# DriverV1_0.net
KiCad netlist of a schematic drawn in Altium Designer
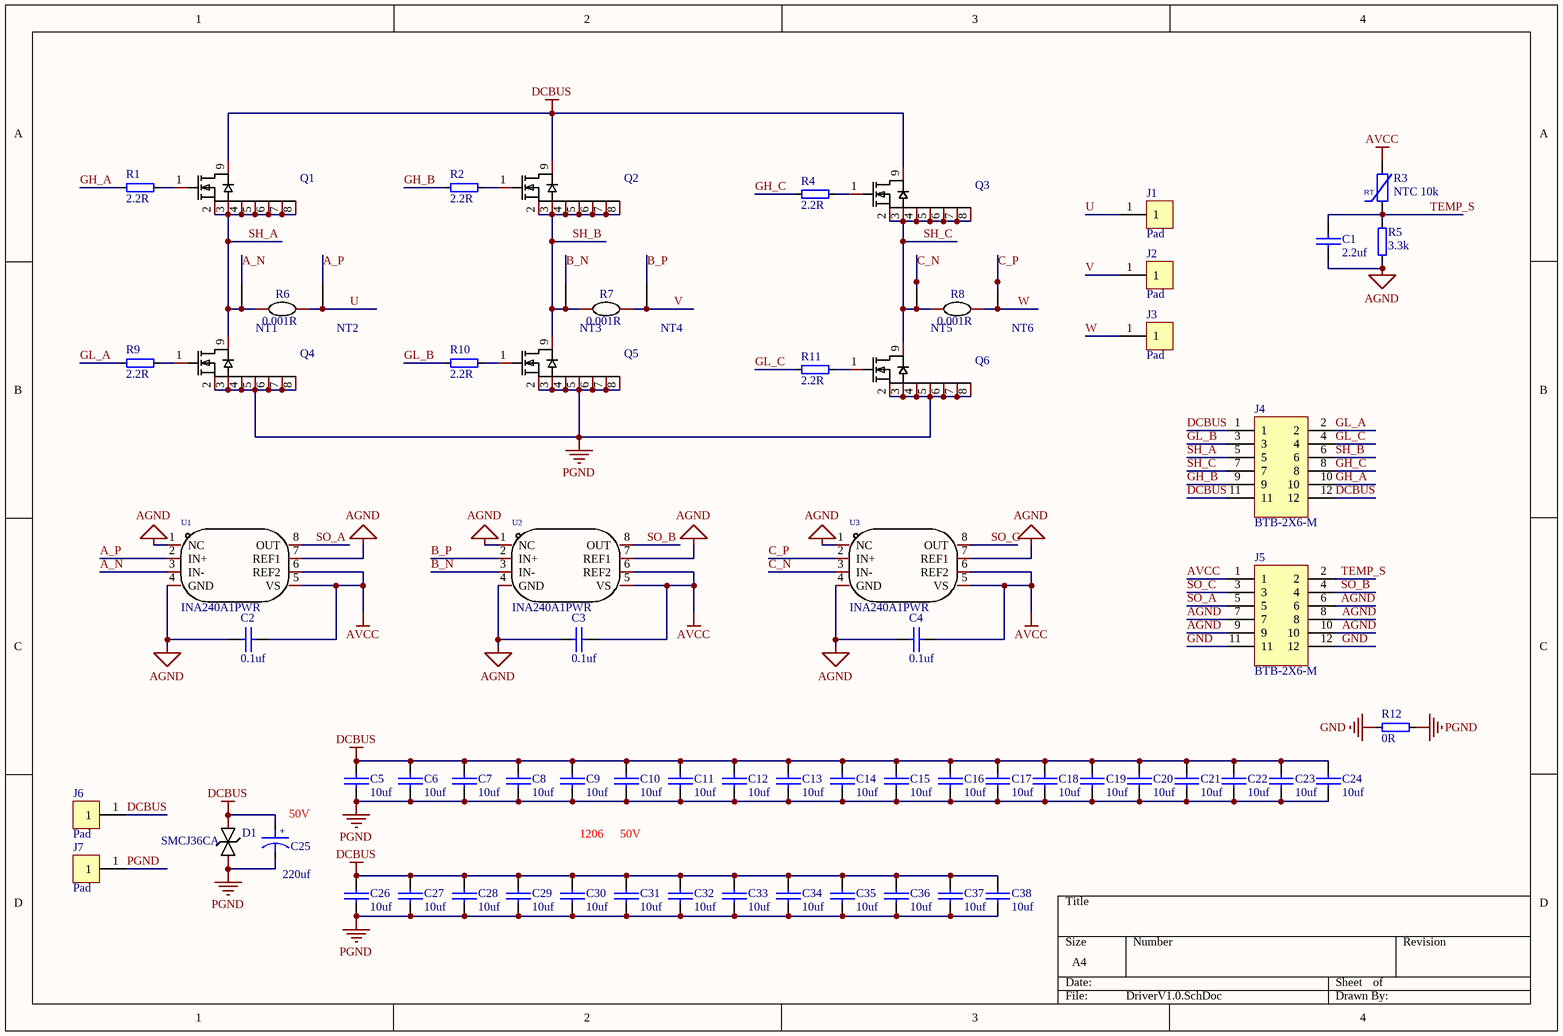
[diagram p0: DriverV1.0.SchDoc]

(export (version "E")
  (design (tool "Eeschema 10.0.6"))
  (components
    (comp (ref "C1")
      (value "2.2uf")
      (footprint "0603C")
      (description "贴片电容")
      (libsource (lib "Driver") (part "CAP"))
    )
    (comp (ref "C2")
      (value "0.1uf")
      (footprint "0603C")
      (description "贴片电容")
      (libsource (lib "Driver") (part "CAP"))
    )
    (comp (ref "C3")
      (value "0.1uf")
      (footprint "0603C")
      (description "贴片电容")
      (libsource (lib "Driver") (part "CAP"))
    )
    (comp (ref "C4")
      (value "0.1uf")
      (footprint "0603C")
      (description "贴片电容")
      (libsource (lib "Driver") (part "CAP"))
    )
    (comp (ref "C5")
      (value "10uf")
      (footprint "1206C")
      (description "贴片电容")
      (libsource (lib "Driver") (part "CAP"))
    )
    (comp (ref "C6")
      (value "10uf")
      (footprint "1206C")
      (description "贴片电容")
      (libsource (lib "Driver") (part "CAP"))
    )
    (comp (ref "C7")
      (value "10uf")
      (footprint "1206C")
      (description "贴片电容")
      (libsource (lib "Driver") (part "CAP"))
    )
    (comp (ref "C8")
      (value "10uf")
      (footprint "1206C")
      (description "贴片电容")
      (libsource (lib "Driver") (part "CAP"))
    )
    (comp (ref "C9")
      (value "10uf")
      (footprint "1206C")
      (description "贴片电容")
      (libsource (lib "Driver") (part "CAP"))
    )
    (comp (ref "C10")
      (value "10uf")
      (footprint "1206C")
      (description "贴片电容")
      (libsource (lib "Driver") (part "CAP"))
    )
    (comp (ref "C11")
      (value "10uf")
      (footprint "1206C")
      (description "贴片电容")
      (libsource (lib "Driver") (part "CAP"))
    )
    (comp (ref "C12")
      (value "10uf")
      (footprint "1206C")
      (description "贴片电容")
      (libsource (lib "Driver") (part "CAP"))
    )
    (comp (ref "C13")
      (value "10uf")
      (footprint "1206C")
      (description "贴片电容")
      (libsource (lib "Driver") (part "CAP"))
    )
    (comp (ref "C14")
      (value "10uf")
      (footprint "1206C")
      (description "贴片电容")
      (libsource (lib "Driver") (part "CAP"))
    )
    (comp (ref "C15")
      (value "10uf")
      (footprint "1206C")
      (description "贴片电容")
      (libsource (lib "Driver") (part "CAP"))
    )
    (comp (ref "C16")
      (value "10uf")
      (footprint "1206C")
      (description "贴片电容")
      (libsource (lib "Driver") (part "CAP"))
    )
    (comp (ref "C17")
      (value "10uf")
      (footprint "1206C")
      (description "贴片电容")
      (libsource (lib "Driver") (part "CAP"))
    )
    (comp (ref "C18")
      (value "10uf")
      (footprint "1206C")
      (description "贴片电容")
      (libsource (lib "Driver") (part "CAP"))
    )
    (comp (ref "C19")
      (value "10uf")
      (footprint "1206C")
      (description "贴片电容")
      (libsource (lib "Driver") (part "CAP"))
    )
    (comp (ref "C20")
      (value "10uf")
      (footprint "1206C")
      (description "贴片电容")
      (libsource (lib "Driver") (part "CAP"))
    )
    (comp (ref "C21")
      (value "10uf")
      (footprint "1206C")
      (description "贴片电容")
      (libsource (lib "Driver") (part "CAP"))
    )
    (comp (ref "C22")
      (value "10uf")
      (footprint "1206C")
      (description "贴片电容")
      (libsource (lib "Driver") (part "CAP"))
    )
    (comp (ref "C23")
      (value "10uf")
      (footprint "1206C")
      (description "贴片电容")
      (libsource (lib "Driver") (part "CAP"))
    )
    (comp (ref "C24")
      (value "10uf")
      (footprint "1206C")
      (description "贴片电容")
      (libsource (lib "Driver") (part "CAP"))
    )
    (comp (ref "C25")
      (value "220uf")
      (footprint "ELECTRO10-5-N")
      (description "极性电容")
      (libsource (lib "Driver") (part "CAP+"))
    )
    (comp (ref "C26")
      (value "10uf")
      (footprint "1206C")
      (description "贴片电容")
      (libsource (lib "Driver") (part "CAP"))
    )
    (comp (ref "C27")
      (value "10uf")
      (footprint "1206C")
      (description "贴片电容")
      (libsource (lib "Driver") (part "CAP"))
    )
    (comp (ref "C28")
      (value "10uf")
      (footprint "1206C")
      (description "贴片电容")
      (libsource (lib "Driver") (part "CAP"))
    )
    (comp (ref "C29")
      (value "10uf")
      (footprint "1206C")
      (description "贴片电容")
      (libsource (lib "Driver") (part "CAP"))
    )
    (comp (ref "C30")
      (value "10uf")
      (footprint "1206C")
      (description "贴片电容")
      (libsource (lib "Driver") (part "CAP"))
    )
    (comp (ref "C31")
      (value "10uf")
      (footprint "1206C")
      (description "贴片电容")
      (libsource (lib "Driver") (part "CAP"))
    )
    (comp (ref "C32")
      (value "10uf")
      (footprint "1206C")
      (description "贴片电容")
      (libsource (lib "Driver") (part "CAP"))
    )
    (comp (ref "C33")
      (value "10uf")
      (footprint "1206C")
      (description "贴片电容")
      (libsource (lib "Driver") (part "CAP"))
    )
    (comp (ref "C34")
      (value "10uf")
      (footprint "1206C")
      (description "贴片电容")
      (libsource (lib "Driver") (part "CAP"))
    )
    (comp (ref "C35")
      (value "10uf")
      (footprint "1206C")
      (description "贴片电容")
      (libsource (lib "Driver") (part "CAP"))
    )
    (comp (ref "C36")
      (value "10uf")
      (footprint "1206C")
      (description "贴片电容")
      (libsource (lib "Driver") (part "CAP"))
    )
    (comp (ref "C37")
      (value "10uf")
      (footprint "1206C")
      (description "贴片电容")
      (libsource (lib "Driver") (part "CAP"))
    )
    (comp (ref "C38")
      (value "10uf")
      (footprint "1206C")
      (description "贴片电容")
      (libsource (lib "Driver") (part "CAP"))
    )
    (comp (ref "D1")
      (value "SMCJ36CA")
      (footprint "SMC")
      (description "极性:双向;")
      (fields (field (name "MANUFACTURER") "TWGMC(台湾迪嘉)") (field (name "MANUFACTURER PART") "SMBJ28CA"))
      (libsource (lib "Driver") (part "SMCJ36CA"))
    )
    (comp (ref "J1")
      (value "Pad")
      (footprint "PAD")
      (description "焊盘")
      (libsource (lib "Driver") (part "Pad"))
    )
    (comp (ref "J2")
      (value "Pad")
      (footprint "PAD")
      (description "焊盘")
      (libsource (lib "Driver") (part "Pad"))
    )
    (comp (ref "J3")
      (value "Pad")
      (footprint "PAD")
      (description "焊盘")
      (libsource (lib "Driver") (part "Pad"))
    )
    (comp (ref "J4")
      (value "BTB-2X6-M")
      (footprint "BTB-M-0.8mm-2x6P")
      (description "0.8间距2x6P公座")
      (libsource (lib "Driver") (part "BTB-2X6-M"))
    )
    (comp (ref "J5")
      (value "BTB-2X6-M")
      (footprint "BTB-M-0.8mm-2x6P")
      (description "0.8间距2x6P公座")
      (libsource (lib "Driver") (part "BTB-2X6-M"))
    )
    (comp (ref "J6") (value "Pad") (footprint "PAD") (description "焊盘") (libsource (lib "") (part "Pad_1")))
    (comp (ref "J7") (value "Pad") (footprint "PAD") (description "焊盘") (libsource (lib "") (part "Pad_1")))
    (comp (ref "NT1")
      (value "0.25mm")
      (footprint "NetTie_0.25mm")
      (libsource (lib "Driver") (part "NetTie_0.25mm"))
    )
    (comp (ref "NT2")
      (value "0.25mm")
      (footprint "NetTie_0.25mm")
      (libsource (lib "Driver") (part "NetTie_0.25mm"))
    )
    (comp (ref "NT3")
      (value "0.25mm")
      (footprint "NetTie_0.25mm")
      (libsource (lib "Driver") (part "NetTie_0.25mm"))
    )
    (comp (ref "NT4")
      (value "0.25mm")
      (footprint "NetTie_0.25mm")
      (libsource (lib "Driver") (part "NetTie_0.25mm"))
    )
    (comp (ref "NT5")
      (value "0.25mm")
      (footprint "NetTie_0.25mm")
      (libsource (lib "Driver") (part "NetTie_0.25mm"))
    )
    (comp (ref "NT6")
      (value "0.25mm")
      (footprint "NetTie_0.25mm")
      (libsource (lib "Driver") (part "NetTie_0.25mm"))
    )
    (comp (ref "Q1")
      (value "HYG006N04LS1TA")
      (footprint "TOLL")
      (description "N沟道增强型MOS 40V-600A")
      (fields (field (name "MANUFACTURER") "HUAYI(华羿微)"))
      (libsource (lib "Driver") (part "HYG006N04LS1TA"))
    )
    (comp (ref "Q2")
      (value "HYG006N04LS1TA")
      (footprint "TOLL")
      (description "N沟道增强型MOS 40V-600A")
      (fields (field (name "MANUFACTURER") "HUAYI(华羿微)"))
      (libsource (lib "Driver") (part "HYG006N04LS1TA"))
    )
    (comp (ref "Q3")
      (value "HYG006N04LS1TA")
      (footprint "TOLL")
      (description "N沟道增强型MOS 40V-600A")
      (fields (field (name "MANUFACTURER") "HUAYI(华羿微)"))
      (libsource (lib "Driver") (part "HYG006N04LS1TA"))
    )
    (comp (ref "Q4")
      (value "HYG006N04LS1TA")
      (footprint "TOLL")
      (description "N沟道增强型MOS 40V-600A")
      (fields (field (name "MANUFACTURER") "HUAYI(华羿微)"))
      (libsource (lib "Driver") (part "HYG006N04LS1TA"))
    )
    (comp (ref "Q5")
      (value "HYG006N04LS1TA")
      (footprint "TOLL")
      (description "N沟道增强型MOS 40V-600A")
      (fields (field (name "MANUFACTURER") "HUAYI(华羿微)"))
      (libsource (lib "Driver") (part "HYG006N04LS1TA"))
    )
    (comp (ref "Q6")
      (value "HYG006N04LS1TA")
      (footprint "TOLL")
      (description "N沟道增强型MOS 40V-600A")
      (fields (field (name "MANUFACTURER") "HUAYI(华羿微)"))
      (libsource (lib "Driver") (part "HYG006N04LS1TA"))
    )
    (comp (ref "R1")
      (value "2.2R")
      (footprint "0603R")
      (description "贴片电阻")
      (libsource (lib "Driver") (part "RES"))
    )
    (comp (ref "R2")
      (value "2.2R")
      (footprint "0603R")
      (description "贴片电阻")
      (libsource (lib "Driver") (part "RES"))
    )
    (comp (ref "R3")
      (value "NTC 10k")
      (footprint "0805R")
      (description "热敏电阻")
      (libsource (lib "Driver") (part "RT"))
    )
    (comp (ref "R4")
      (value "2.2R")
      (footprint "0603R")
      (description "贴片电阻")
      (libsource (lib "Driver") (part "RES"))
    )
    (comp (ref "R5")
      (value "3.3k")
      (footprint "0603R")
      (description "贴片电阻")
      (libsource (lib "Driver") (part "RES"))
    )
    (comp (ref "R6")
      (value "0.001R")
      (footprint "3920R")
      (description "采样电阻")
      (fields (field (name "MANUFACTURER") "RESI(开步睿思）") (field (name "MANUFACTURER PART") "SEWF3920F1L00P9"))
      (libsource (lib "Driver") (part "HoLRS3920"))
    )
    (comp (ref "R7")
      (value "0.001R")
      (footprint "3920R")
      (description "采样电阻")
      (fields (field (name "MANUFACTURER") "RESI(开步睿思）") (field (name "MANUFACTURER PART") "SEWF3920F1L00P9"))
      (libsource (lib "Driver") (part "HoLRS3920"))
    )
    (comp (ref "R8")
      (value "0.001R")
      (footprint "3920R")
      (description "采样电阻")
      (fields (field (name "MANUFACTURER") "RESI(开步睿思）") (field (name "MANUFACTURER PART") "SEWF3920F1L00P9"))
      (libsource (lib "Driver") (part "HoLRS3920"))
    )
    (comp (ref "R9")
      (value "2.2R")
      (footprint "0603R")
      (description "贴片电阻")
      (libsource (lib "Driver") (part "RES"))
    )
    (comp (ref "R10")
      (value "2.2R")
      (footprint "0603R")
      (description "贴片电阻")
      (libsource (lib "Driver") (part "RES"))
    )
    (comp (ref "R11")
      (value "2.2R")
      (footprint "0603R")
      (description "贴片电阻")
      (libsource (lib "Driver") (part "RES"))
    )
    (comp (ref "R12")
      (value "0R")
      (footprint "0603R")
      (description "贴片电阻")
      (libsource (lib "Driver") (part "RES"))
    )
    (comp (ref "U1")
      (value "INA240A1PWR")
      (footprint "TSSOP-8")
      (fields (field (name "MANUFACTURER") "TI(德州仪器)") (field (name "NAME") "INA240A1PWR"))
      (libsource (lib "Driver") (part "INA240A1PWR"))
    )
    (comp (ref "U2")
      (value "INA240A1PWR")
      (footprint "TSSOP-8")
      (fields (field (name "MANUFACTURER") "TI(德州仪器)") (field (name "NAME") "INA240A1PWR"))
      (libsource (lib "Driver") (part "INA240A1PWR"))
    )
    (comp (ref "U3")
      (value "INA240A1PWR")
      (footprint "TSSOP-8")
      (fields (field (name "MANUFACTURER") "TI(德州仪器)") (field (name "NAME") "INA240A1PWR"))
      (libsource (lib "Driver") (part "INA240A1PWR"))
    )
  )
  (nets
    (net (code "1") (name "/A_N") (class "Default")
      (node (ref "NT1") (pin "2") (pinfunction "2_2") (pintype "passive"))
      (node (ref "U1") (pin "3") (pinfunction "IN-_3") (pintype "passive"))
    )
    (net (code "2") (name "/A_P") (class "Default")
      (node (ref "NT2") (pin "2") (pinfunction "2_2") (pintype "passive"))
      (node (ref "U1") (pin "2") (pinfunction "IN+_2") (pintype "passive"))
    )
    (net (code "3") (name "/B_N") (class "Default")
      (node (ref "NT3") (pin "2") (pinfunction "2_2") (pintype "passive"))
      (node (ref "U2") (pin "3") (pinfunction "IN-_3") (pintype "passive"))
    )
    (net (code "4") (name "/B_P") (class "Default")
      (node (ref "NT4") (pin "2") (pinfunction "2_2") (pintype "passive"))
      (node (ref "U2") (pin "2") (pinfunction "IN+_2") (pintype "passive"))
    )
    (net (code "5") (name "/C_N") (class "Default")
      (node (ref "NT5") (pin "2") (pinfunction "2_2") (pintype "passive"))
      (node (ref "U3") (pin "3") (pinfunction "IN-_3") (pintype "passive"))
    )
    (net (code "6") (name "/C_P") (class "Default")
      (node (ref "NT6") (pin "2") (pinfunction "2_2") (pintype "passive"))
      (node (ref "U3") (pin "2") (pinfunction "IN+_2") (pintype "passive"))
    )
    (net (code "7") (name "/GH_A") (class "Default")
      (node (ref "J4") (pin "10") (pinfunction "10_10") (pintype "passive"))
      (node (ref "R1") (pin "1") (pinfunction "1_1") (pintype "passive"))
    )
    (net (code "8") (name "/GH_B") (class "Default")
      (node (ref "J4") (pin "9") (pinfunction "9_9") (pintype "passive"))
      (node (ref "R2") (pin "1") (pinfunction "1_1") (pintype "passive"))
    )
    (net (code "9") (name "/GH_C") (class "Default")
      (node (ref "J4") (pin "8") (pinfunction "8_8") (pintype "passive"))
      (node (ref "R4") (pin "1") (pinfunction "1_1") (pintype "passive"))
    )
    (net (code "10") (name "/GL_A") (class "Default")
      (node (ref "J4") (pin "2") (pinfunction "2_2") (pintype "passive"))
      (node (ref "R9") (pin "1") (pinfunction "1_1") (pintype "passive"))
    )
    (net (code "11") (name "/GL_B") (class "Default")
      (node (ref "J4") (pin "3") (pinfunction "3_3") (pintype "passive"))
      (node (ref "R10") (pin "1") (pinfunction "1_1") (pintype "passive"))
    )
    (net (code "12") (name "/GL_C") (class "Default")
      (node (ref "J4") (pin "4") (pinfunction "4_4") (pintype "passive"))
      (node (ref "R11") (pin "1") (pinfunction "1_1") (pintype "passive"))
    )
    (net (code "13") (name "/SH_A") (class "Default")
      (node (ref "J4") (pin "5") (pinfunction "5_5") (pintype "passive"))
      (node (ref "NT1") (pin "1") (pintype "passive"))
      (node (ref "Q1") (pin "2") (pinfunction "S_2") (pintype "passive"))
      (node (ref "Q1") (pin "3") (pinfunction "S_3") (pintype "passive"))
      (node (ref "Q1") (pin "4") (pinfunction "S_4") (pintype "passive"))
      (node (ref "Q1") (pin "5") (pinfunction "S_5") (pintype "passive"))
      (node (ref "Q1") (pin "6") (pinfunction "S_6") (pintype "passive"))
      (node (ref "Q1") (pin "7") (pinfunction "S_7") (pintype "passive"))
      (node (ref "Q1") (pin "8") (pinfunction "S_8") (pintype "passive"))
      (node (ref "Q4") (pin "9") (pinfunction "D_9") (pintype "passive"))
      (node (ref "R6") (pin "2") (pinfunction "2_2") (pintype "passive"))
    )
    (net (code "14") (name "/SH_B") (class "Default")
      (node (ref "J4") (pin "6") (pinfunction "6_6") (pintype "passive"))
      (node (ref "NT3") (pin "1") (pintype "passive"))
      (node (ref "Q2") (pin "2") (pinfunction "S_2") (pintype "passive"))
      (node (ref "Q2") (pin "3") (pinfunction "S_3") (pintype "passive"))
      (node (ref "Q2") (pin "4") (pinfunction "S_4") (pintype "passive"))
      (node (ref "Q2") (pin "5") (pinfunction "S_5") (pintype "passive"))
      (node (ref "Q2") (pin "6") (pinfunction "S_6") (pintype "passive"))
      (node (ref "Q2") (pin "7") (pinfunction "S_7") (pintype "passive"))
      (node (ref "Q2") (pin "8") (pinfunction "S_8") (pintype "passive"))
      (node (ref "Q5") (pin "9") (pinfunction "D_9") (pintype "passive"))
      (node (ref "R7") (pin "2") (pinfunction "2_2") (pintype "passive"))
    )
    (net (code "15") (name "/SH_C") (class "Default")
      (node (ref "J4") (pin "7") (pinfunction "7_7") (pintype "passive"))
      (node (ref "NT5") (pin "1") (pintype "passive"))
      (node (ref "Q3") (pin "2") (pinfunction "S_2") (pintype "passive"))
      (node (ref "Q3") (pin "3") (pinfunction "S_3") (pintype "passive"))
      (node (ref "Q3") (pin "4") (pinfunction "S_4") (pintype "passive"))
      (node (ref "Q3") (pin "5") (pinfunction "S_5") (pintype "passive"))
      (node (ref "Q3") (pin "6") (pinfunction "S_6") (pintype "passive"))
      (node (ref "Q3") (pin "7") (pinfunction "S_7") (pintype "passive"))
      (node (ref "Q3") (pin "8") (pinfunction "S_8") (pintype "passive"))
      (node (ref "Q6") (pin "9") (pinfunction "D_9") (pintype "passive"))
      (node (ref "R8") (pin "2") (pinfunction "2_2") (pintype "passive"))
    )
    (net (code "16") (name "/SO_A") (class "Default")
      (node (ref "J5") (pin "5") (pinfunction "5_5") (pintype "passive"))
      (node (ref "U1") (pin "8") (pinfunction "OUT_8") (pintype "passive"))
    )
    (net (code "17") (name "/SO_B") (class "Default")
      (node (ref "J5") (pin "4") (pinfunction "4_4") (pintype "passive"))
      (node (ref "U2") (pin "8") (pinfunction "OUT_8") (pintype "passive"))
    )
    (net (code "18") (name "/SO_C") (class "Default")
      (node (ref "J5") (pin "3") (pinfunction "3_3") (pintype "passive"))
      (node (ref "U3") (pin "8") (pinfunction "OUT_8") (pintype "passive"))
    )
    (net (code "19") (name "/TEMP_S") (class "Default")
      (node (ref "C1") (pin "1") (pinfunction "1_1") (pintype "passive"))
      (node (ref "J5") (pin "2") (pinfunction "2_2") (pintype "passive"))
      (node (ref "R3") (pin "1") (pinfunction "1_1") (pintype "passive"))
      (node (ref "R5") (pin "2") (pinfunction "2_2") (pintype "passive"))
    )
    (net (code "20") (name "/U") (class "Default")
      (node (ref "J1") (pin "1") (pinfunction "1_1") (pintype "passive"))
      (node (ref "NT2") (pin "1") (pintype "passive"))
      (node (ref "R6") (pin "1") (pinfunction "1_1") (pintype "passive"))
    )
    (net (code "21") (name "/V") (class "Default")
      (node (ref "J2") (pin "1") (pinfunction "1_1") (pintype "passive"))
      (node (ref "NT4") (pin "1") (pintype "passive"))
      (node (ref "R7") (pin "1") (pinfunction "1_1") (pintype "passive"))
    )
    (net (code "22") (name "/W") (class "Default")
      (node (ref "J3") (pin "1") (pinfunction "1_1") (pintype "passive"))
      (node (ref "NT6") (pin "1") (pintype "passive"))
      (node (ref "R8") (pin "1") (pinfunction "1_1") (pintype "passive"))
    )
    (net (code "23") (name "AGND") (class "Default")
      (node (ref "C1") (pin "2") (pinfunction "2_2") (pintype "passive"))
      (node (ref "C2") (pin "1") (pinfunction "1_1") (pintype "passive"))
      (node (ref "C3") (pin "1") (pinfunction "1_1") (pintype "passive"))
      (node (ref "C4") (pin "1") (pinfunction "1_1") (pintype "passive"))
      (node (ref "J5") (pin "10") (pinfunction "10_10") (pintype "passive"))
      (node (ref "J5") (pin "6") (pinfunction "6_6") (pintype "passive"))
      (node (ref "J5") (pin "7") (pinfunction "7_7") (pintype "passive"))
      (node (ref "J5") (pin "8") (pinfunction "8_8") (pintype "passive"))
      (node (ref "J5") (pin "9") (pinfunction "9_9") (pintype "passive"))
      (node (ref "R5") (pin "1") (pinfunction "1_1") (pintype "passive"))
      (node (ref "U1") (pin "1") (pinfunction "NC_1") (pintype "passive"))
      (node (ref "U1") (pin "4") (pinfunction "GND_4") (pintype "passive"))
      (node (ref "U1") (pin "7") (pinfunction "REF1_7") (pintype "passive"))
      (node (ref "U2") (pin "1") (pinfunction "NC_1") (pintype "passive"))
      (node (ref "U2") (pin "4") (pinfunction "GND_4") (pintype "passive"))
      (node (ref "U2") (pin "7") (pinfunction "REF1_7") (pintype "passive"))
      (node (ref "U3") (pin "1") (pinfunction "NC_1") (pintype "passive"))
      (node (ref "U3") (pin "4") (pinfunction "GND_4") (pintype "passive"))
      (node (ref "U3") (pin "7") (pinfunction "REF1_7") (pintype "passive"))
    )
    (net (code "24") (name "AVCC") (class "Default")
      (node (ref "C2") (pin "2") (pinfunction "2_2") (pintype "passive"))
      (node (ref "C3") (pin "2") (pinfunction "2_2") (pintype "passive"))
      (node (ref "C4") (pin "2") (pinfunction "2_2") (pintype "passive"))
      (node (ref "J5") (pin "1") (pinfunction "1_1") (pintype "passive"))
      (node (ref "R3") (pin "2") (pinfunction "2_2") (pintype "passive"))
      (node (ref "U1") (pin "5") (pinfunction "VS_5") (pintype "passive"))
      (node (ref "U1") (pin "6") (pinfunction "REF2_6") (pintype "passive"))
      (node (ref "U2") (pin "5") (pinfunction "VS_5") (pintype "passive"))
      (node (ref "U2") (pin "6") (pinfunction "REF2_6") (pintype "passive"))
      (node (ref "U3") (pin "5") (pinfunction "VS_5") (pintype "passive"))
      (node (ref "U3") (pin "6") (pinfunction "REF2_6") (pintype "passive"))
    )
    (net (code "25") (name "DCBUS") (class "Default")
      (node (ref "C10") (pin "1") (pinfunction "1_1") (pintype "passive"))
      (node (ref "C11") (pin "1") (pinfunction "1_1") (pintype "passive"))
      (node (ref "C12") (pin "1") (pinfunction "1_1") (pintype "passive"))
      (node (ref "C13") (pin "1") (pinfunction "1_1") (pintype "passive"))
      (node (ref "C14") (pin "1") (pinfunction "1_1") (pintype "passive"))
      (node (ref "C15") (pin "1") (pinfunction "1_1") (pintype "passive"))
      (node (ref "C16") (pin "1") (pinfunction "1_1") (pintype "passive"))
      (node (ref "C17") (pin "1") (pinfunction "1_1") (pintype "passive"))
      (node (ref "C18") (pin "1") (pinfunction "1_1") (pintype "passive"))
      (node (ref "C19") (pin "1") (pinfunction "1_1") (pintype "passive"))
      (node (ref "C20") (pin "1") (pinfunction "1_1") (pintype "passive"))
      (node (ref "C21") (pin "1") (pinfunction "1_1") (pintype "passive"))
      (node (ref "C22") (pin "1") (pinfunction "1_1") (pintype "passive"))
      (node (ref "C23") (pin "1") (pinfunction "1_1") (pintype "passive"))
      (node (ref "C24") (pin "1") (pinfunction "1_1") (pintype "passive"))
      (node (ref "C25") (pin "1") (pinfunction "1_1") (pintype "passive"))
      (node (ref "C26") (pin "1") (pinfunction "1_1") (pintype "passive"))
      (node (ref "C27") (pin "1") (pinfunction "1_1") (pintype "passive"))
      (node (ref "C28") (pin "1") (pinfunction "1_1") (pintype "passive"))
      (node (ref "C29") (pin "1") (pinfunction "1_1") (pintype "passive"))
      (node (ref "C30") (pin "1") (pinfunction "1_1") (pintype "passive"))
      (node (ref "C31") (pin "1") (pinfunction "1_1") (pintype "passive"))
      (node (ref "C32") (pin "1") (pinfunction "1_1") (pintype "passive"))
      (node (ref "C33") (pin "1") (pinfunction "1_1") (pintype "passive"))
      (node (ref "C34") (pin "1") (pinfunction "1_1") (pintype "passive"))
      (node (ref "C35") (pin "1") (pinfunction "1_1") (pintype "passive"))
      (node (ref "C36") (pin "1") (pinfunction "1_1") (pintype "passive"))
      (node (ref "C37") (pin "1") (pinfunction "1_1") (pintype "passive"))
      (node (ref "C38") (pin "1") (pinfunction "1_1") (pintype "passive"))
      (node (ref "C5") (pin "1") (pinfunction "1_1") (pintype "passive"))
      (node (ref "C6") (pin "1") (pinfunction "1_1") (pintype "passive"))
      (node (ref "C7") (pin "1") (pinfunction "1_1") (pintype "passive"))
      (node (ref "C8") (pin "1") (pinfunction "1_1") (pintype "passive"))
      (node (ref "C9") (pin "1") (pinfunction "1_1") (pintype "passive"))
      (node (ref "D1") (pin "2") (pinfunction "2_2") (pintype "passive"))
      (node (ref "J4") (pin "1") (pinfunction "1_1") (pintype "passive"))
      (node (ref "J4") (pin "11") (pinfunction "11_11") (pintype "passive"))
      (node (ref "J4") (pin "12") (pinfunction "12_12") (pintype "passive"))
      (node (ref "J6") (pin "1") (pinfunction "1_1") (pintype "passive"))
      (node (ref "Q1") (pin "9") (pinfunction "D_9") (pintype "passive"))
      (node (ref "Q2") (pin "9") (pinfunction "D_9") (pintype "passive"))
      (node (ref "Q3") (pin "9") (pinfunction "D_9") (pintype "passive"))
    )
    (net (code "26") (name "GND") (class "Default")
      (node (ref "J5") (pin "11") (pinfunction "11_11") (pintype "passive"))
      (node (ref "J5") (pin "12") (pinfunction "12_12") (pintype "passive"))
      (node (ref "R12") (pin "2") (pinfunction "2_2") (pintype "passive"))
    )
    (net (code "27") (name "Net-(Q1-G)") (class "Default")
      (node (ref "Q1") (pin "1") (pinfunction "G_1") (pintype "passive"))
      (node (ref "R1") (pin "2") (pinfunction "2_2") (pintype "passive"))
    )
    (net (code "28") (name "Net-(Q2-G)") (class "Default")
      (node (ref "Q2") (pin "1") (pinfunction "G_1") (pintype "passive"))
      (node (ref "R2") (pin "2") (pinfunction "2_2") (pintype "passive"))
    )
    (net (code "29") (name "Net-(Q3-G)") (class "Default")
      (node (ref "Q3") (pin "1") (pinfunction "G_1") (pintype "passive"))
      (node (ref "R4") (pin "2") (pinfunction "2_2") (pintype "passive"))
    )
    (net (code "30") (name "Net-(Q4-G)") (class "Default")
      (node (ref "Q4") (pin "1") (pinfunction "G_1") (pintype "passive"))
      (node (ref "R9") (pin "2") (pinfunction "2_2") (pintype "passive"))
    )
    (net (code "31") (name "Net-(Q5-G)") (class "Default")
      (node (ref "Q5") (pin "1") (pinfunction "G_1") (pintype "passive"))
      (node (ref "R10") (pin "2") (pinfunction "2_2") (pintype "passive"))
    )
    (net (code "32") (name "Net-(Q6-G)") (class "Default")
      (node (ref "Q6") (pin "1") (pinfunction "G_1") (pintype "passive"))
      (node (ref "R11") (pin "2") (pinfunction "2_2") (pintype "passive"))
    )
    (net (code "33") (name "PGND") (class "Default")
      (node (ref "C10") (pin "2") (pinfunction "2_2") (pintype "passive"))
      (node (ref "C11") (pin "2") (pinfunction "2_2") (pintype "passive"))
      (node (ref "C12") (pin "2") (pinfunction "2_2") (pintype "passive"))
      (node (ref "C13") (pin "2") (pinfunction "2_2") (pintype "passive"))
      (node (ref "C14") (pin "2") (pinfunction "2_2") (pintype "passive"))
      (node (ref "C15") (pin "2") (pinfunction "2_2") (pintype "passive"))
      (node (ref "C16") (pin "2") (pinfunction "2_2") (pintype "passive"))
      (node (ref "C17") (pin "2") (pinfunction "2_2") (pintype "passive"))
      (node (ref "C18") (pin "2") (pinfunction "2_2") (pintype "passive"))
      (node (ref "C19") (pin "2") (pinfunction "2_2") (pintype "passive"))
      (node (ref "C20") (pin "2") (pinfunction "2_2") (pintype "passive"))
      (node (ref "C21") (pin "2") (pinfunction "2_2") (pintype "passive"))
      (node (ref "C22") (pin "2") (pinfunction "2_2") (pintype "passive"))
      (node (ref "C23") (pin "2") (pinfunction "2_2") (pintype "passive"))
      (node (ref "C24") (pin "2") (pinfunction "2_2") (pintype "passive"))
      (node (ref "C25") (pin "2") (pinfunction "2_2") (pintype "passive"))
      (node (ref "C26") (pin "2") (pinfunction "2_2") (pintype "passive"))
      (node (ref "C27") (pin "2") (pinfunction "2_2") (pintype "passive"))
      (node (ref "C28") (pin "2") (pinfunction "2_2") (pintype "passive"))
      (node (ref "C29") (pin "2") (pinfunction "2_2") (pintype "passive"))
      (node (ref "C30") (pin "2") (pinfunction "2_2") (pintype "passive"))
      (node (ref "C31") (pin "2") (pinfunction "2_2") (pintype "passive"))
      (node (ref "C32") (pin "2") (pinfunction "2_2") (pintype "passive"))
      (node (ref "C33") (pin "2") (pinfunction "2_2") (pintype "passive"))
      (node (ref "C34") (pin "2") (pinfunction "2_2") (pintype "passive"))
      (node (ref "C35") (pin "2") (pinfunction "2_2") (pintype "passive"))
      (node (ref "C36") (pin "2") (pinfunction "2_2") (pintype "passive"))
      (node (ref "C37") (pin "2") (pinfunction "2_2") (pintype "passive"))
      (node (ref "C38") (pin "2") (pinfunction "2_2") (pintype "passive"))
      (node (ref "C5") (pin "2") (pinfunction "2_2") (pintype "passive"))
      (node (ref "C6") (pin "2") (pinfunction "2_2") (pintype "passive"))
      (node (ref "C7") (pin "2") (pinfunction "2_2") (pintype "passive"))
      (node (ref "C8") (pin "2") (pinfunction "2_2") (pintype "passive"))
      (node (ref "C9") (pin "2") (pinfunction "2_2") (pintype "passive"))
      (node (ref "D1") (pin "1") (pinfunction "1_1") (pintype "passive"))
      (node (ref "J7") (pin "1") (pinfunction "1_1") (pintype "passive"))
      (node (ref "Q4") (pin "2") (pinfunction "S_2") (pintype "passive"))
      (node (ref "Q4") (pin "3") (pinfunction "S_3") (pintype "passive"))
      (node (ref "Q4") (pin "4") (pinfunction "S_4") (pintype "passive"))
      (node (ref "Q4") (pin "5") (pinfunction "S_5") (pintype "passive"))
      (node (ref "Q4") (pin "6") (pinfunction "S_6") (pintype "passive"))
      (node (ref "Q4") (pin "7") (pinfunction "S_7") (pintype "passive"))
      (node (ref "Q4") (pin "8") (pinfunction "S_8") (pintype "passive"))
      (node (ref "Q5") (pin "2") (pinfunction "S_2") (pintype "passive"))
      (node (ref "Q5") (pin "3") (pinfunction "S_3") (pintype "passive"))
      (node (ref "Q5") (pin "4") (pinfunction "S_4") (pintype "passive"))
      (node (ref "Q5") (pin "5") (pinfunction "S_5") (pintype "passive"))
      (node (ref "Q5") (pin "6") (pinfunction "S_6") (pintype "passive"))
      (node (ref "Q5") (pin "7") (pinfunction "S_7") (pintype "passive"))
      (node (ref "Q5") (pin "8") (pinfunction "S_8") (pintype "passive"))
      (node (ref "Q6") (pin "2") (pinfunction "S_2") (pintype "passive"))
      (node (ref "Q6") (pin "3") (pinfunction "S_3") (pintype "passive"))
      (node (ref "Q6") (pin "4") (pinfunction "S_4") (pintype "passive"))
      (node (ref "Q6") (pin "5") (pinfunction "S_5") (pintype "passive"))
      (node (ref "Q6") (pin "6") (pinfunction "S_6") (pintype "passive"))
      (node (ref "Q6") (pin "7") (pinfunction "S_7") (pintype "passive"))
      (node (ref "Q6") (pin "8") (pinfunction "S_8") (pintype "passive"))
      (node (ref "R12") (pin "1") (pinfunction "1_1") (pintype "passive"))
    )
  )
)
